# schemTSC.net
KiCad netlist of a schematic drawn in EAGLE
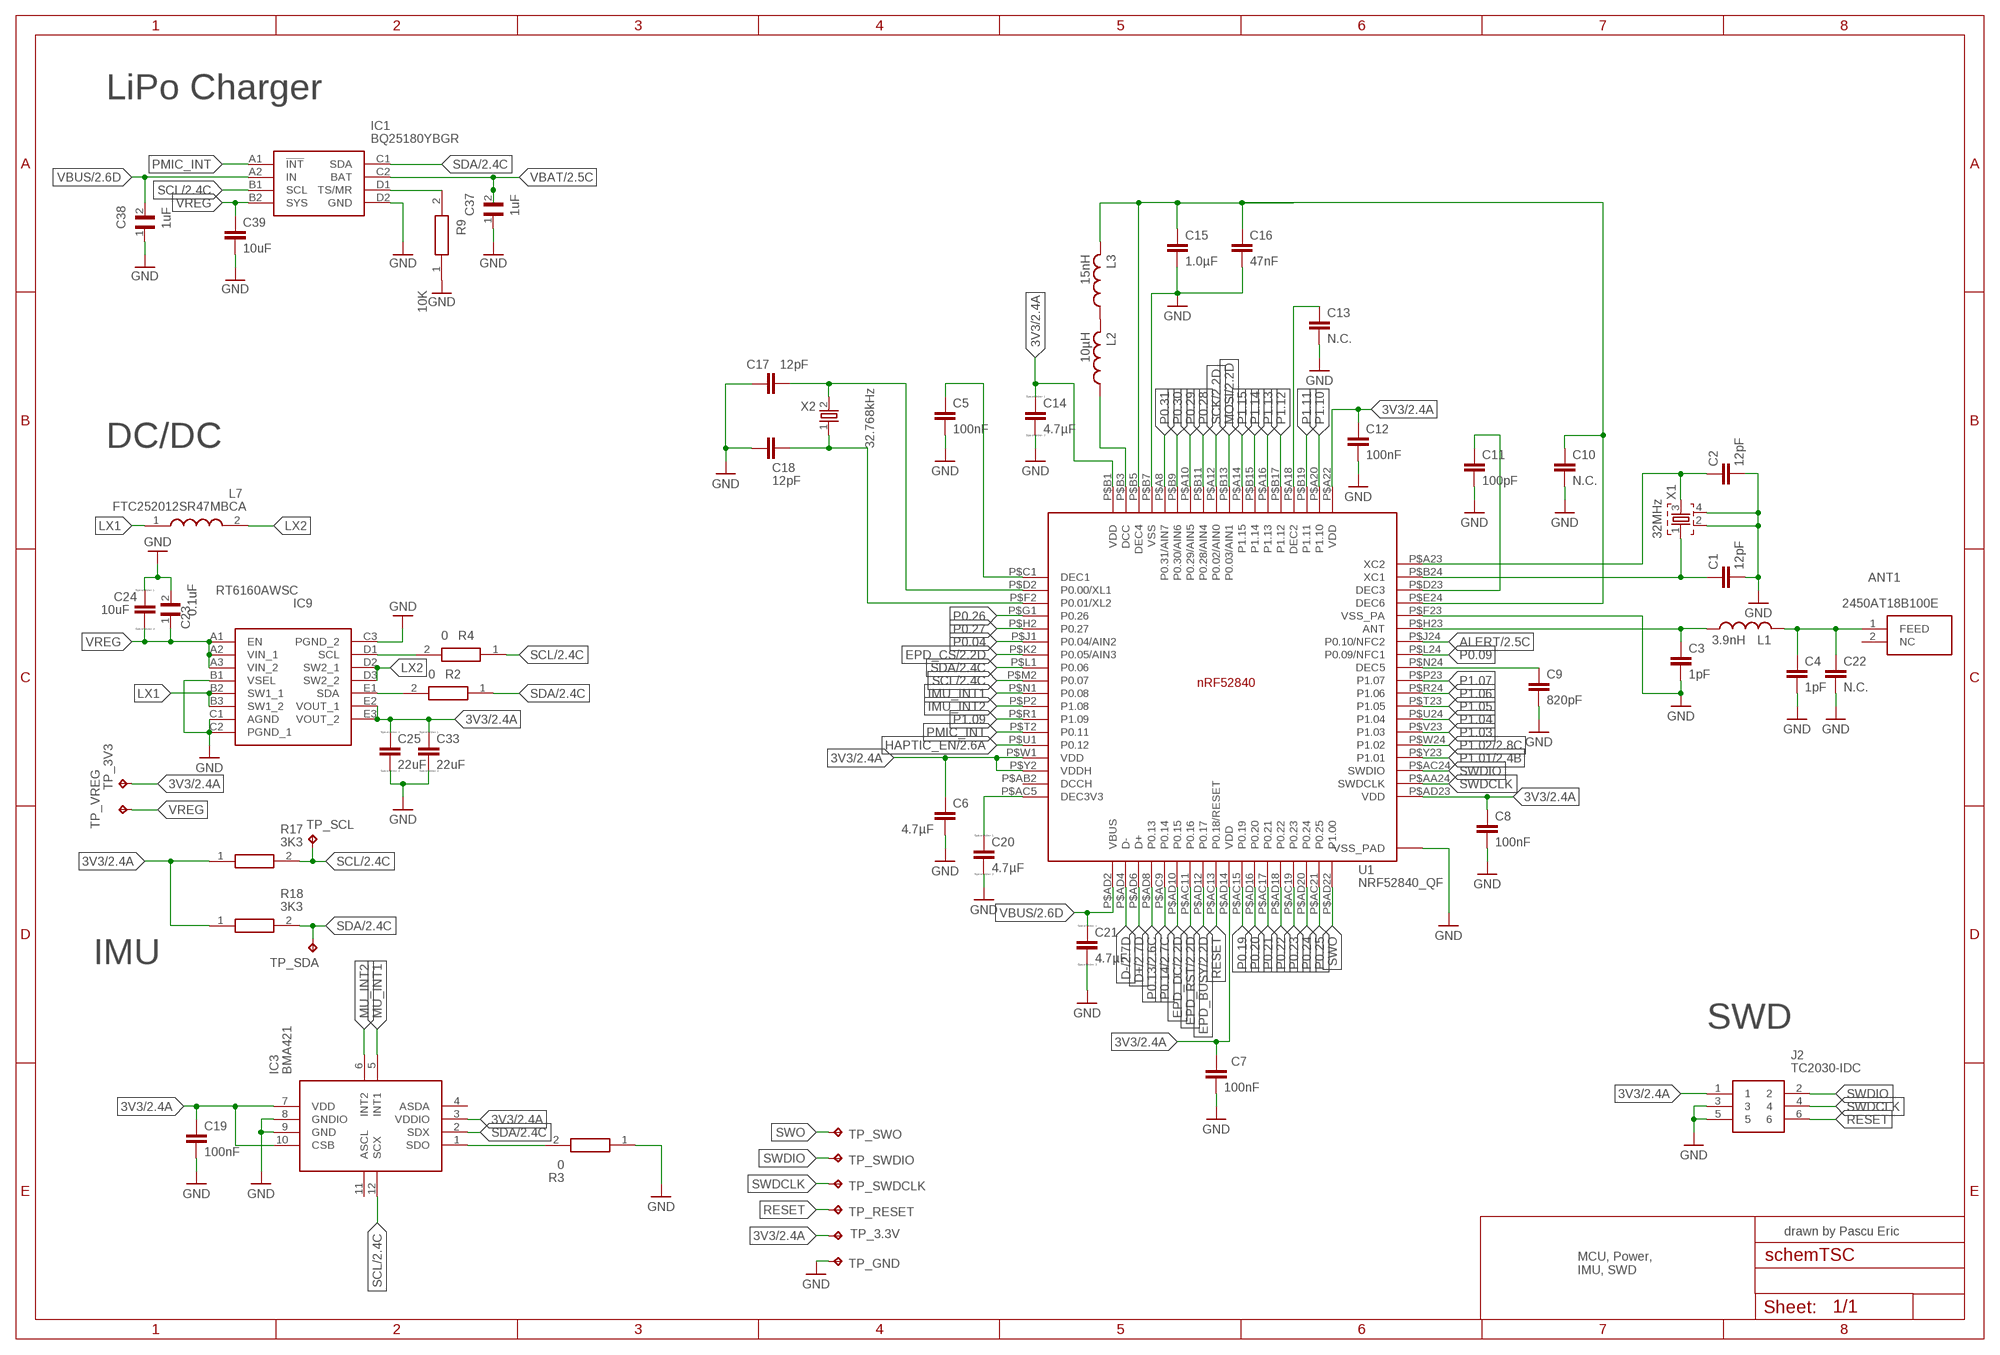
[diagram p0: schematic, sheet 1, part 1 of 2]
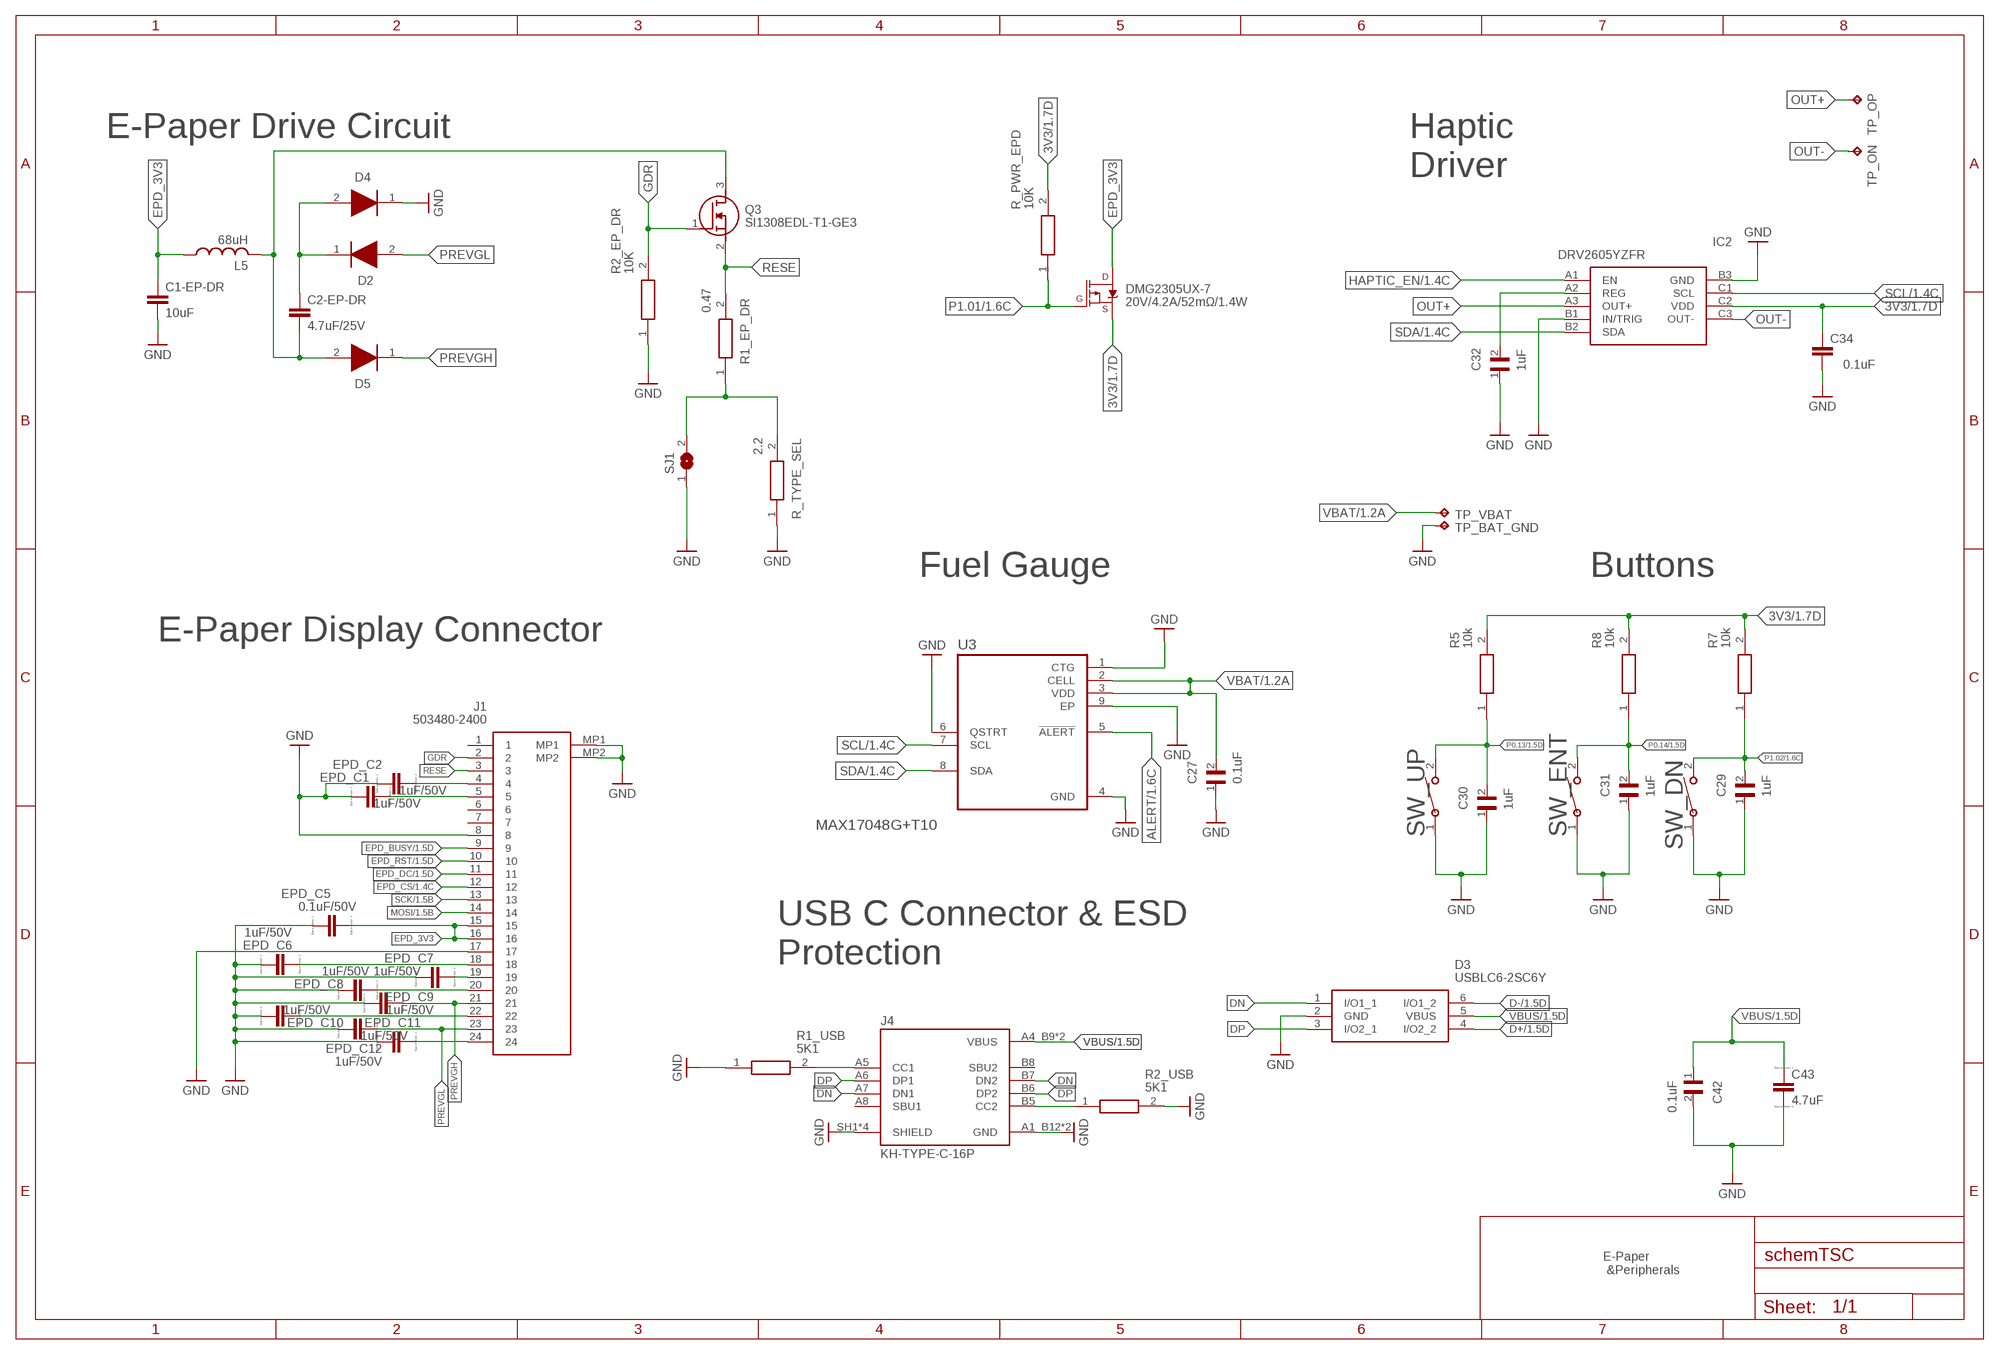
[diagram p1: schematic, sheet 1, part 2 of 2]

(export (version "E")
  (design (tool "Eeschema 10.0.6"))
  (components
    (comp (ref "ANT1")
      (value "2450AT18B100E")
      (footprint "eagle-import:2450AT18B100E_ANTC3216X140N")
      (fields (field (name "MOUSER_PART_NUMBER") "609-2450AT18B100E"))
      (libsource (lib "eagle-import") (part "2450AT18B100E_2450AT18B100E"))
    )
    (comp (ref "C1")
      (value "12pF")
      (footprint "eagle-import:NORDIC_NRF_3_RESC0201_L")
      (libsource (lib "eagle-import") (part "NORDIC_NRF_3_CAPACITOR_0201_L"))
    )
    (comp (ref "C1-EP-DR")
      (value "10uF")
      (footprint "eagle-import:NORDIC_NRF_3_RESC0201_L")
      (libsource (lib "eagle-import") (part "NORDIC_NRF_3_CAPACITOR_0201_L"))
    )
    (comp (ref "C2")
      (value "12pF")
      (footprint "eagle-import:NORDIC_NRF_3_RESC0201_L")
      (libsource (lib "eagle-import") (part "NORDIC_NRF_3_CAPACITOR_0201_L"))
    )
    (comp (ref "C2-EP-DR")
      (value "4.7uF/25V")
      (footprint "eagle-import:NORDIC_NRF_3_RESC0201_L")
      (libsource (lib "eagle-import") (part "NORDIC_NRF_3_CAPACITOR_0201_L"))
    )
    (comp (ref "C3")
      (value "1pF")
      (footprint "eagle-import:NORDIC_NRF_3_RESC0201_L")
      (libsource (lib "eagle-import") (part "NORDIC_NRF_3_CAPACITOR_0201_L"))
    )
    (comp (ref "C4")
      (value "1pF")
      (footprint "eagle-import:NORDIC_NRF_3_RESC0201_L")
      (libsource (lib "eagle-import") (part "NORDIC_NRF_3_CAPACITOR_0201_L"))
    )
    (comp (ref "C5")
      (value "100nF")
      (footprint "eagle-import:NORDIC_NRF_3_RESC0201_L")
      (libsource (lib "eagle-import") (part "NORDIC_NRF_3_CAPACITOR_0201_L"))
    )
    (comp (ref "C6")
      (value "4.7µF")
      (footprint "eagle-import:NORDIC_NRF_3_RESC0201_L")
      (libsource (lib "eagle-import") (part "NORDIC_NRF_3_CAPACITOR_0201_L"))
    )
    (comp (ref "C7")
      (value "100nF")
      (footprint "eagle-import:NORDIC_NRF_3_RESC0201_L")
      (libsource (lib "eagle-import") (part "NORDIC_NRF_3_CAPACITOR_0201_L"))
    )
    (comp (ref "C8")
      (value "100nF")
      (footprint "eagle-import:NORDIC_NRF_3_RESC0201_L")
      (libsource (lib "eagle-import") (part "NORDIC_NRF_3_CAPACITOR_0201_L"))
    )
    (comp (ref "C9")
      (value "820pF")
      (footprint "eagle-import:NORDIC_NRF_3_RESC0201_L")
      (libsource (lib "eagle-import") (part "NORDIC_NRF_3_CAPACITOR_0201_L"))
    )
    (comp (ref "C10")
      (value "N.C.")
      (footprint "eagle-import:NORDIC_NRF_3_RESC0201_L")
      (libsource (lib "eagle-import") (part "NORDIC_NRF_3_CAPACITOR_0201_L"))
    )
    (comp (ref "C11")
      (value "100pF")
      (footprint "eagle-import:NORDIC_NRF_3_RESC0201_L")
      (libsource (lib "eagle-import") (part "NORDIC_NRF_3_CAPACITOR_0201_L"))
    )
    (comp (ref "C12")
      (value "100nF")
      (footprint "eagle-import:NORDIC_NRF_3_RESC0201_L")
      (libsource (lib "eagle-import") (part "NORDIC_NRF_3_CAPACITOR_0201_L"))
    )
    (comp (ref "C13")
      (value "N.C.")
      (footprint "eagle-import:NORDIC_NRF_3_RESC0201_L")
      (libsource (lib "eagle-import") (part "NORDIC_NRF_3_CAPACITOR_0201_L"))
    )
    (comp (ref "C14")
      (value "4.7µF")
      (footprint "eagle-import:ESP32_C6_LIBRARY_1_ESP32_WROVER_EAGLE-LTSPICE_C0402")
      (libsource (lib "eagle-import") (part "ESP32_C6_LIBRARY_1_ESP32_WROVER_EAGLE-LTSPICE_CC0402"))
    )
    (comp (ref "C15")
      (value "1.0µF")
      (footprint "eagle-import:NORDIC_NRF_3_RESC0201_L")
      (libsource (lib "eagle-import") (part "NORDIC_NRF_3_CAPACITOR_0201_L"))
    )
    (comp (ref "C16")
      (value "47nF")
      (footprint "eagle-import:NORDIC_NRF_3_RESC0201_L")
      (libsource (lib "eagle-import") (part "NORDIC_NRF_3_CAPACITOR_0201_L"))
    )
    (comp (ref "C17")
      (value "12pF")
      (footprint "eagle-import:NORDIC_NRF_3_RESC0201_L")
      (libsource (lib "eagle-import") (part "NORDIC_NRF_3_CAPACITOR_0201_L"))
    )
    (comp (ref "C18")
      (value "12pF")
      (footprint "eagle-import:NORDIC_NRF_3_RESC0201_L")
      (libsource (lib "eagle-import") (part "NORDIC_NRF_3_CAPACITOR_0201_L"))
    )
    (comp (ref "C19")
      (value "100nF")
      (footprint "eagle-import:NORDIC_NRF_3_RESC0201_L")
      (libsource (lib "eagle-import") (part "NORDIC_NRF_3_CAPACITOR_0201_L"))
    )
    (comp (ref "C20")
      (value "4.7µF")
      (footprint "eagle-import:ESP32_C6_LIBRARY_1_ESP32_WROVER_EAGLE-LTSPICE_C0402")
      (libsource (lib "eagle-import") (part "ESP32_C6_LIBRARY_1_ESP32_WROVER_EAGLE-LTSPICE_CC0402"))
    )
    (comp (ref "C21")
      (value "4.7µF")
      (footprint "eagle-import:ESP32_C6_LIBRARY_1_ESP32_WROVER_EAGLE-LTSPICE_C0402")
      (libsource (lib "eagle-import") (part "ESP32_C6_LIBRARY_1_ESP32_WROVER_EAGLE-LTSPICE_CC0402"))
    )
    (comp (ref "C22")
      (value "N.C.")
      (footprint "eagle-import:NORDIC_NRF_3_RESC0201_L")
      (libsource (lib "eagle-import") (part "NORDIC_NRF_3_CAPACITOR_0201_L"))
    )
    (comp (ref "C23")
      (value "0.1uF")
      (footprint "eagle-import:GRM011R60J152KE01L_2_CAPC0201X13N")
      (fields (field (name "MF") "Murata") (field (name "MP") "GRM011R60J152KE01L"))
      (libsource (lib "eagle-import") (part "GRM011R60J152KE01L_2_GRM011R60J152KE01L"))
    )
    (comp (ref "C24")
      (value "10uF")
      (footprint "eagle-import:ESP32_C6_LIBRARY_1_ESP32_WROVER_EAGLE-LTSPICE_C0402")
      (libsource (lib "eagle-import") (part "ESP32_C6_LIBRARY_1_ESP32_WROVER_EAGLE-LTSPICE_CC0402"))
    )
    (comp (ref "C25")
      (value "22uF")
      (footprint "eagle-import:ESP32_C6_LIBRARY_1_ESP32_WROVER_EAGLE-LTSPICE_C0402")
      (libsource (lib "eagle-import") (part "ESP32_C6_LIBRARY_1_ESP32_WROVER_EAGLE-LTSPICE_CC0402"))
    )
    (comp (ref "C27")
      (value "0.1uF")
      (footprint "eagle-import:GRM011R60J152KE01L_2_CAPC0201X13N")
      (fields (field (name "MF") "Murata") (field (name "MP") "GRM011R60J152KE01L"))
      (libsource (lib "eagle-import") (part "GRM011R60J152KE01L_2_GRM011R60J152KE01L"))
    )
    (comp (ref "C29")
      (value "1uF")
      (footprint "eagle-import:GRM011R60J152KE01L_2_CAPC0201X13N")
      (fields (field (name "MF") "Murata") (field (name "MP") "GRM011R60J152KE01L"))
      (libsource (lib "eagle-import") (part "GRM011R60J152KE01L_2_GRM011R60J152KE01L"))
    )
    (comp (ref "C30")
      (value "1uF")
      (footprint "eagle-import:GRM011R60J152KE01L_2_CAPC0201X13N")
      (fields (field (name "MF") "Murata") (field (name "MP") "GRM011R60J152KE01L"))
      (libsource (lib "eagle-import") (part "GRM011R60J152KE01L_2_GRM011R60J152KE01L"))
    )
    (comp (ref "C31")
      (value "1uF")
      (footprint "eagle-import:GRM011R60J152KE01L_2_CAPC0201X13N")
      (fields (field (name "MF") "Murata") (field (name "MP") "GRM011R60J152KE01L"))
      (libsource (lib "eagle-import") (part "GRM011R60J152KE01L_2_GRM011R60J152KE01L"))
    )
    (comp (ref "C32")
      (value "1uF")
      (footprint "eagle-import:GRM011R60J152KE01L_2_CAPC0201X13N")
      (fields (field (name "MF") "Murata") (field (name "MP") "GRM011R60J152KE01L"))
      (libsource (lib "eagle-import") (part "GRM011R60J152KE01L_2_GRM011R60J152KE01L"))
    )
    (comp (ref "C33")
      (value "22uF")
      (footprint "eagle-import:ESP32_C6_LIBRARY_1_ESP32_WROVER_EAGLE-LTSPICE_C0402")
      (libsource (lib "eagle-import") (part "ESP32_C6_LIBRARY_1_ESP32_WROVER_EAGLE-LTSPICE_CC0402"))
    )
    (comp (ref "C34")
      (value "0.1uF")
      (footprint "eagle-import:NORDIC_NRF_3_RESC0201_L")
      (libsource (lib "eagle-import") (part "NORDIC_NRF_3_CAPACITOR_0201_L"))
    )
    (comp (ref "C37")
      (value "1uF")
      (footprint "eagle-import:GRM011R60J152KE01L_2_CAPC0201X13N")
      (fields (field (name "MF") "Murata") (field (name "MP") "GRM011R60J152KE01L"))
      (libsource (lib "eagle-import") (part "GRM011R60J152KE01L_2_GRM011R60J152KE01L"))
    )
    (comp (ref "C38")
      (value "1uF")
      (footprint "eagle-import:GRM011R60J152KE01L_2_CAPC0201X13N")
      (fields (field (name "MF") "Murata") (field (name "MP") "GRM011R60J152KE01L"))
      (libsource (lib "eagle-import") (part "GRM011R60J152KE01L_2_GRM011R60J152KE01L"))
    )
    (comp (ref "C39")
      (value "10uF")
      (footprint "eagle-import:NORDIC_NRF_3_RESC0201_L")
      (libsource (lib "eagle-import") (part "NORDIC_NRF_3_CAPACITOR_0201_L"))
    )
    (comp (ref "C42")
      (value "0.1uF")
      (footprint "eagle-import:GRM011R60J152KE01L_2_CAPC0201X13N")
      (fields (field (name "MF") "Murata") (field (name "MP") "GRM011R60J152KE01L"))
      (libsource (lib "eagle-import") (part "GRM011R60J152KE01L_2_GRM011R60J152KE01L"))
    )
    (comp (ref "C43")
      (value "4.7uF")
      (footprint "eagle-import:ESP32_C6_LIBRARY_1_ESP32_WROVER_EAGLE-LTSPICE_C0402")
      (libsource (lib "eagle-import") (part "ESP32_C6_LIBRARY_1_ESP32_WROVER_EAGLE-LTSPICE_CC0402"))
    )
    (comp (ref "D2")
      (value "ESP32_C6_LIBRARY_5_MBR0530")
      (footprint "eagle-import:ESP32_C6_LIBRARY_5_SOD3716X135N")
      (fields (field (name "MF") "ON Semiconductor") (field (name "MP") "MBR0530"))
      (libsource (lib "eagle-import") (part "ESP32_C6_LIBRARY_5_MBR0530"))
    )
    (comp (ref "D3")
      (value "USBLC6-2SC6Y")
      (footprint "eagle-import:ESP32_C6_LIBRARY_3_SOT95P280X145-6N")
      (fields (field (name "MF") "STMicroelectronics"))
      (libsource (lib "eagle-import") (part "ESP32_C6_LIBRARY_3_USBLC6-2SC6Y"))
    )
    (comp (ref "D4")
      (value "ESP32_C6_LIBRARY_5_MBR0530")
      (footprint "eagle-import:ESP32_C6_LIBRARY_5_SOD3716X135N")
      (fields (field (name "MF") "ON Semiconductor") (field (name "MP") "MBR0530"))
      (libsource (lib "eagle-import") (part "ESP32_C6_LIBRARY_5_MBR0530"))
    )
    (comp (ref "D5")
      (value "ESP32_C6_LIBRARY_5_MBR0530")
      (footprint "eagle-import:ESP32_C6_LIBRARY_5_SOD3716X135N")
      (fields (field (name "MF") "ON Semiconductor") (field (name "MP") "MBR0530"))
      (libsource (lib "eagle-import") (part "ESP32_C6_LIBRARY_5_MBR0530"))
    )
    (comp (ref "DMG2305UX-7")
      (value "20V/4.2A/52mΩ/1.4W")
      (footprint "eagle-import:ESP32_C6_LIBRARY_4_ESP32_C6_LIBRARY_4_ESP32_C6_LIBRARY_4_ESP32_C6_LIBRARY_4_ESP32_WROVER_SPARKFUN-DISCRETESEMI_SOT23-3")
      (libsource (lib "eagle-import") (part "ESP32_C6_LIBRARY_4_ESP32_WROVER_SPARKFUN-DISCRETESEMI_MOSFET_PCH-DMG2305UX-7"))
    )
    (comp (ref "EPD_C1")
      (value "1uF/50V")
      (footprint "eagle-import:ESP32_C6_LIBRARY_1_ESP32_WROVER_EAGLE-LTSPICE_C0402")
      (libsource (lib "eagle-import") (part "ESP32_C6_LIBRARY_1_ESP32_WROVER_EAGLE-LTSPICE_CC0402"))
    )
    (comp (ref "EPD_C2")
      (value "1uF/50V")
      (footprint "eagle-import:ESP32_C6_LIBRARY_1_ESP32_WROVER_EAGLE-LTSPICE_C0402")
      (libsource (lib "eagle-import") (part "ESP32_C6_LIBRARY_1_ESP32_WROVER_EAGLE-LTSPICE_CC0402"))
    )
    (comp (ref "EPD_C5")
      (value "0.1uF/50V")
      (footprint "eagle-import:ESP32_C6_LIBRARY_1_ESP32_WROVER_EAGLE-LTSPICE_C0402")
      (libsource (lib "eagle-import") (part "ESP32_C6_LIBRARY_1_ESP32_WROVER_EAGLE-LTSPICE_CC0402"))
    )
    (comp (ref "EPD_C6")
      (value "1uF/50V")
      (footprint "eagle-import:ESP32_C6_LIBRARY_1_ESP32_WROVER_EAGLE-LTSPICE_C0402")
      (libsource (lib "eagle-import") (part "ESP32_C6_LIBRARY_1_ESP32_WROVER_EAGLE-LTSPICE_CC0402"))
    )
    (comp (ref "EPD_C7")
      (value "1uF/50V")
      (footprint "eagle-import:ESP32_C6_LIBRARY_1_ESP32_WROVER_EAGLE-LTSPICE_C0402")
      (libsource (lib "eagle-import") (part "ESP32_C6_LIBRARY_1_ESP32_WROVER_EAGLE-LTSPICE_CC0402"))
    )
    (comp (ref "EPD_C8")
      (value "1uF/50V")
      (footprint "eagle-import:ESP32_C6_LIBRARY_1_ESP32_WROVER_EAGLE-LTSPICE_C0402")
      (libsource (lib "eagle-import") (part "ESP32_C6_LIBRARY_1_ESP32_WROVER_EAGLE-LTSPICE_CC0402"))
    )
    (comp (ref "EPD_C9")
      (value "1uF/50V")
      (footprint "eagle-import:ESP32_C6_LIBRARY_1_ESP32_WROVER_EAGLE-LTSPICE_C0402")
      (libsource (lib "eagle-import") (part "ESP32_C6_LIBRARY_1_ESP32_WROVER_EAGLE-LTSPICE_CC0402"))
    )
    (comp (ref "EPD_C10")
      (value "1uF/50V")
      (footprint "eagle-import:ESP32_C6_LIBRARY_1_ESP32_WROVER_EAGLE-LTSPICE_C0402")
      (libsource (lib "eagle-import") (part "ESP32_C6_LIBRARY_1_ESP32_WROVER_EAGLE-LTSPICE_CC0402"))
    )
    (comp (ref "EPD_C11")
      (value "1uF/50V")
      (footprint "eagle-import:ESP32_C6_LIBRARY_1_ESP32_WROVER_EAGLE-LTSPICE_C0402")
      (libsource (lib "eagle-import") (part "ESP32_C6_LIBRARY_1_ESP32_WROVER_EAGLE-LTSPICE_CC0402"))
    )
    (comp (ref "EPD_C12")
      (value "1uF/50V")
      (footprint "eagle-import:ESP32_C6_LIBRARY_1_ESP32_WROVER_EAGLE-LTSPICE_C0402")
      (libsource (lib "eagle-import") (part "ESP32_C6_LIBRARY_1_ESP32_WROVER_EAGLE-LTSPICE_CC0402"))
    )
    (comp (ref "IC1")
      (value "BQ25180YBGR")
      (footprint "eagle-import:BQ25180YBGR_BGA8C40P2X4_100X155X50")
      (fields (field (name "MOUSER_PART_NUMBER") "595-BQ25180YBGR"))
      (libsource (lib "eagle-import") (part "BQ25180YBGR_BQ25180YBGR"))
    )
    (comp (ref "IC2")
      (value "DRV2605YZFR")
      (footprint "eagle-import:DRV2605YZFR_BGA9C50P3X3_144X144X62")
      (libsource (lib "eagle-import") (part "DRV2605YZFR_DRV2605YZFR"))
    )
    (comp (ref "IC3")
      (value "BMA421")
      (footprint "eagle-import:BMA423_BMA423")
      (fields
        (field (name "MANUFACTURER_PART_NUMBER") "BMA423")
        (field (name "MOUSER_PART_NUMBER") "262-BMA423")
      )
      (libsource (lib "eagle-import") (part "BMA423_BMA423"))
    )
    (comp (ref "IC9")
      (value "RT6160AWSC")
      (footprint "eagle-import:RT6160AWSC_BGA15C40P3X5_140X230X60")
      (fields (field (name "MOUSER_PART_NUMBER") "835-RT6160AWSC"))
      (libsource (lib "eagle-import") (part "RT6160AWSC_RT6160AWSC"))
    )
    (comp (ref "J1")
      (value "503480-2400")
      (footprint "eagle-import:503480-2400_5034802400")
      (fields (field (name "MOUSER_PART_NUMBER") "538-503480-2400"))
      (libsource (lib "eagle-import") (part "503480-2400_503480-2400"))
    )
    (comp (ref "J2")
      (value "TC2030-IDC")
      (footprint "eagle-import:TC2030-IDC_TC2030IDC")
      (libsource (lib "eagle-import") (part "TC2030-IDC_TC2030-IDC"))
    )
    (comp (ref "J4")
      (value "KH-TYPE-C-16P")
      (footprint "eagle-import:KH-TYPE-C-16P_KINGHELM_KH-TYPE-C-16P")
      (fields (field (name "MF") "kinghelm"))
      (libsource (lib "eagle-import") (part "KH-TYPE-C-16P_KH-TYPE-C-16P"))
    )
    (comp (ref "L1")
      (value "3.9nH")
      (footprint "eagle-import:NORDIC_NRF_2_RESC0402_L")
      (libsource (lib "eagle-import") (part "NORDIC_NRF_2_INDUCTOR_0402_L"))
    )
    (comp (ref "L2")
      (value "10µH")
      (footprint "eagle-import:NORDIC_NRF_2_RESC0402_L")
      (libsource (lib "eagle-import") (part "NORDIC_NRF_2_INDUCTOR_0402_L"))
    )
    (comp (ref "L3")
      (value "15nH")
      (footprint "eagle-import:NORDIC_NRF_2_RESC0402_L")
      (libsource (lib "eagle-import") (part "NORDIC_NRF_2_INDUCTOR_0402_L"))
    )
    (comp (ref "L5")
      (value "68uH")
      (footprint "eagle-import:NORDIC_NRF_2_RESC0402_L")
      (libsource (lib "eagle-import") (part "NORDIC_NRF_2_INDUCTOR_0402_L"))
    )
    (comp (ref "L7")
      (value "FTC252012SR47MBCA")
      (footprint "eagle-import:MLP2016SR47MT0S1_INDC2016X100N")
      (libsource (lib "eagle-import") (part "MLP2016SR47MT0S1_FTC252012SR47MBCA"))
    )
    (comp (ref "Q3")
      (value "SI1308EDL-T1-GE3")
      (footprint "eagle-import:ESP32_C6_LIBRARY_6_SOT65P210X110-3N")
      (fields (field (name "MF") "Vishay Siliconix"))
      (libsource (lib "eagle-import") (part "ESP32_C6_LIBRARY_6_SI1308EDL-T1-GE3"))
    )
    (comp (ref "R1_EP_DR")
      (value "0.47")
      (footprint "eagle-import:ERA-1AEB3401C_0201")
      (libsource (lib "eagle-import") (part "ERA-1AEB3401C_CPF0201D7K68C1"))
    )
    (comp (ref "R1_USB")
      (value "5K1")
      (footprint "eagle-import:CPF0201D7K68C1_0201")
      (libsource (lib "eagle-import") (part "CPF0201D7K68C1_CPF0201D7K68C1"))
    )
    (comp (ref "R2")
      (value "0")
      (footprint "eagle-import:CPF0201D7K68C1_0201")
      (libsource (lib "eagle-import") (part "CPF0201D7K68C1_CPF0201D7K68C1"))
    )
    (comp (ref "R2_EP_DR")
      (value "10K")
      (footprint "eagle-import:ERA-1AEB3401C_0201")
      (libsource (lib "eagle-import") (part "ERA-1AEB3401C_CPF0201D7K68C1"))
    )
    (comp (ref "R2_USB")
      (value "5K1")
      (footprint "eagle-import:ERA-1AEB3401C_0201")
      (libsource (lib "eagle-import") (part "ERA-1AEB3401C_CPF0201D7K68C1"))
    )
    (comp (ref "R3")
      (value "0")
      (footprint "eagle-import:ERA-1AEB3401C_0201")
      (libsource (lib "eagle-import") (part "ERA-1AEB3401C_CPF0201D7K68C1"))
    )
    (comp (ref "R4")
      (value "0")
      (footprint "eagle-import:CPF0201D7K68C1_0201")
      (libsource (lib "eagle-import") (part "CPF0201D7K68C1_CPF0201D7K68C1"))
    )
    (comp (ref "R5")
      (value "10k")
      (footprint "eagle-import:CPF0201D7K68C1_0201")
      (libsource (lib "eagle-import") (part "CPF0201D7K68C1_CPF0201D7K68C1"))
    )
    (comp (ref "R7")
      (value "10k")
      (footprint "eagle-import:CPF0201D7K68C1_0201")
      (libsource (lib "eagle-import") (part "CPF0201D7K68C1_CPF0201D7K68C1"))
    )
    (comp (ref "R8")
      (value "10k")
      (footprint "eagle-import:CPF0201D7K68C1_0201")
      (libsource (lib "eagle-import") (part "CPF0201D7K68C1_CPF0201D7K68C1"))
    )
    (comp (ref "R9")
      (value "10K")
      (footprint "eagle-import:ERA-1AEB3401C_0201")
      (libsource (lib "eagle-import") (part "ERA-1AEB3401C_CPF0201D7K68C1"))
    )
    (comp (ref "R17")
      (value "3K3")
      (footprint "eagle-import:CPF0201D7K68C1_0201")
      (libsource (lib "eagle-import") (part "CPF0201D7K68C1_CPF0201D7K68C1"))
    )
    (comp (ref "R18")
      (value "3K3")
      (footprint "eagle-import:CPF0201D7K68C1_0201")
      (libsource (lib "eagle-import") (part "CPF0201D7K68C1_CPF0201D7K68C1"))
    )
    (comp (ref "R_PWR_EPD")
      (value "10K")
      (footprint "eagle-import:CPF0201D7K68C1_0201")
      (libsource (lib "eagle-import") (part "CPF0201D7K68C1_CPF0201D7K68C1"))
    )
    (comp (ref "R_TYPE_SEL")
      (value "2.2")
      (footprint "eagle-import:ERA-1AEB3401C_0201")
      (libsource (lib "eagle-import") (part "ERA-1AEB3401C_CPF0201D7K68C1"))
    )
    (comp (ref "SJ1")
      (value "ESP32_C6_LIBRARY_7_JUMPER_SJ")
      (footprint "eagle-import:ESP32_C6_LIBRARY_7_JUMPER_SJ")
      (libsource (lib "eagle-import") (part "ESP32_C6_LIBRARY_7_JUMPER_SJ"))
    )
    (comp (ref "SW_DN")
      (value "2025-10-22_07-23-44_LIBRARY_EVP-AKE31ASW_EVP-AKE31A_PAN")
      (footprint "eagle-import:2025-10-22_07-23-44_LIBRARY_SW_EVP-AKE31A_PAN")
      (fields
        (field (name "MANUFACTURER_PART_NUMBER") "EVP-AKE31A")
        (field (name "COPYRIGHT") "Copyright (C) 2025 Ultra Librarian. All rights reserved.")
      )
      (libsource (lib "eagle-import") (part "2025-10-22_07-23-44_LIBRARY_EVP-AKE31ASW_EVP-AKE31A_PAN"))
    )
    (comp (ref "SW_ENT")
      (value "2025-10-22_07-23-44_LIBRARY_EVP-AKE31ASW_EVP-AKE31A_PAN")
      (footprint "eagle-import:2025-10-22_07-23-44_LIBRARY_SW_EVP-AKE31A_PAN")
      (fields
        (field (name "MANUFACTURER_PART_NUMBER") "EVP-AKE31A")
        (field (name "COPYRIGHT") "Copyright (C) 2025 Ultra Librarian. All rights reserved.")
      )
      (libsource (lib "eagle-import") (part "2025-10-22_07-23-44_LIBRARY_EVP-AKE31ASW_EVP-AKE31A_PAN"))
    )
    (comp (ref "SW_UP")
      (value "2025-10-22_07-23-44_LIBRARY_EVP-AKE31ASW_EVP-AKE31A_PAN")
      (footprint "eagle-import:2025-10-22_07-23-44_LIBRARY_SW_EVP-AKE31A_PAN")
      (fields
        (field (name "MANUFACTURER_PART_NUMBER") "EVP-AKE31A")
        (field (name "COPYRIGHT") "Copyright (C) 2025 Ultra Librarian. All rights reserved.")
      )
      (libsource (lib "eagle-import") (part "2025-10-22_07-23-44_LIBRARY_EVP-AKE31ASW_EVP-AKE31A_PAN"))
    )
    (comp (ref "TP_3.3V")
      (value "HECTOR_WATCH_1_TPTP20R")
      (footprint "eagle-import:HECTOR_WATCH_1_TP20R")
      (libsource (lib "eagle-import") (part "HECTOR_WATCH_1_TPTP20R"))
    )
    (comp (ref "TP_3V3")
      (value "HECTOR_WATCH_1_TPTP20R")
      (footprint "eagle-import:HECTOR_WATCH_1_TP20R")
      (libsource (lib "eagle-import") (part "HECTOR_WATCH_1_TPTP20R"))
    )
    (comp (ref "TP_BAT_GND")
      (value "HECTOR_WATCH_1_TPTP20R")
      (footprint "eagle-import:HECTOR_WATCH_1_TP20R")
      (libsource (lib "eagle-import") (part "HECTOR_WATCH_1_TPTP20R"))
    )
    (comp (ref "TP_GND")
      (value "HECTOR_WATCH_1_TPTP20R")
      (footprint "eagle-import:HECTOR_WATCH_1_TP20R")
      (libsource (lib "eagle-import") (part "HECTOR_WATCH_1_TPTP20R"))
    )
    (comp (ref "TP_ON")
      (value "HECTOR_WATCH_1_TPTP20R")
      (footprint "eagle-import:HECTOR_WATCH_1_TP20R")
      (libsource (lib "eagle-import") (part "HECTOR_WATCH_1_TPTP20R"))
    )
    (comp (ref "TP_OP")
      (value "HECTOR_WATCH_1_TPTP20R")
      (footprint "eagle-import:HECTOR_WATCH_1_TP20R")
      (libsource (lib "eagle-import") (part "HECTOR_WATCH_1_TPTP20R"))
    )
    (comp (ref "TP_RESET")
      (value "HECTOR_WATCH_1_TPTP20R")
      (footprint "eagle-import:HECTOR_WATCH_1_TP20R")
      (libsource (lib "eagle-import") (part "HECTOR_WATCH_1_TPTP20R"))
    )
    (comp (ref "TP_SCL")
      (value "HECTOR_WATCH_1_TPTP20R")
      (footprint "eagle-import:HECTOR_WATCH_1_TP20R")
      (libsource (lib "eagle-import") (part "HECTOR_WATCH_1_TPTP20R"))
    )
    (comp (ref "TP_SDA")
      (value "HECTOR_WATCH_1_TPTP20R")
      (footprint "eagle-import:HECTOR_WATCH_1_TP20R")
      (libsource (lib "eagle-import") (part "HECTOR_WATCH_1_TPTP20R"))
    )
    (comp (ref "TP_SWDCLK")
      (value "HECTOR_WATCH_1_TPTP20R")
      (footprint "eagle-import:HECTOR_WATCH_1_TP20R")
      (libsource (lib "eagle-import") (part "HECTOR_WATCH_1_TPTP20R"))
    )
    (comp (ref "TP_SWDIO")
      (value "HECTOR_WATCH_1_TPTP20R")
      (footprint "eagle-import:HECTOR_WATCH_1_TP20R")
      (libsource (lib "eagle-import") (part "HECTOR_WATCH_1_TPTP20R"))
    )
    (comp (ref "TP_SWO")
      (value "HECTOR_WATCH_1_TPTP20R")
      (footprint "eagle-import:HECTOR_WATCH_1_TP20R")
      (libsource (lib "eagle-import") (part "HECTOR_WATCH_1_TPTP20R"))
    )
    (comp (ref "TP_VBAT")
      (value "HECTOR_WATCH_1_TPTP20R")
      (footprint "eagle-import:HECTOR_WATCH_1_TP20R")
      (libsource (lib "eagle-import") (part "HECTOR_WATCH_1_TPTP20R"))
    )
    (comp (ref "TP_VREG")
      (value "HECTOR_WATCH_1_TPTP20R")
      (footprint "eagle-import:HECTOR_WATCH_1_TP20R")
      (libsource (lib "eagle-import") (part "HECTOR_WATCH_1_TPTP20R"))
    )
    (comp (ref "U1")
      (value "NRF52840_QF")
      (footprint "eagle-import:NORDIC_NRF_4_AQFN50P700X700X85_HS-74N")
      (libsource (lib "eagle-import") (part "NORDIC_NRF_4_NRF52840_QF"))
    )
    (comp (ref "U3")
      (value "MAX17048G+T10")
      (footprint "eagle-import:ESP32_C6_LIBRARY_SON50P200X200X80-9N")
      (fields (field (name "MF") "Analog Devices"))
      (libsource (lib "eagle-import") (part "ESP32_C6_LIBRARY_MAX17048G+T10"))
    )
    (comp (ref "X1")
      (value "32MHz")
      (footprint "eagle-import:NORDIC_NRF_BT-XTAL_2016_N")
      (libsource (lib "eagle-import") (part "NORDIC_NRF_XTAL_32MHZ"))
    )
    (comp (ref "X2")
      (value "32.768kHz")
      (footprint "eagle-import:NORDIC_NRF_1_XTAL_3215_N")
      (libsource (lib "eagle-import") (part "NORDIC_NRF_1_XTAL_32KHZ"))
    )
  )
  (nets
    (net (code "1") (name "3V3{slash}1.7D") (class "Default")
      (node (ref "C34") (pin "1") (pinfunction "1_1") (pintype "passive"))
      (node (ref "DMG2305UX-7") (pin "2") (pinfunction "S_2") (pintype "bidirectional"))
      (node (ref "IC2") (pin "C2") (pinfunction "VDD_C2") (pintype "bidirectional"))
      (node (ref "R5") (pin "2") (pinfunction "2_2") (pintype "bidirectional"))
      (node (ref "R7") (pin "2") (pinfunction "2_2") (pintype "bidirectional"))
      (node (ref "R8") (pin "2") (pinfunction "2_2") (pintype "bidirectional"))
      (node (ref "R_PWR_EPD") (pin "2") (pinfunction "2_2") (pintype "bidirectional"))
    )
    (net (code "2") (name "3V3{slash}2.4A") (class "Default")
      (node (ref "C12") (pin "1") (pinfunction "1_1") (pintype "passive"))
      (node (ref "C14") (pin "1") (pinfunction "1_1") (pintype "passive"))
      (node (ref "C19") (pin "1") (pinfunction "1_1") (pintype "passive"))
      (node (ref "C25") (pin "1") (pinfunction "1_1") (pintype "passive"))
      (node (ref "C33") (pin "1") (pinfunction "1_1") (pintype "passive"))
      (node (ref "C6") (pin "1") (pinfunction "1_1") (pintype "passive"))
      (node (ref "C7") (pin "1") (pinfunction "1_1") (pintype "passive"))
      (node (ref "C8") (pin "1") (pinfunction "1_1") (pintype "passive"))
      (node (ref "IC3") (pin "10") (pinfunction "CSB_10") (pintype "bidirectional"))
      (node (ref "IC3") (pin "3") (pinfunction "VDDIO_3") (pintype "bidirectional"))
      (node (ref "IC3") (pin "7") (pinfunction "VDD_7") (pintype "bidirectional"))
      (node (ref "IC9") (pin "E2") (pinfunction "VOUT_1_E2") (pintype "bidirectional"))
      (node (ref "IC9") (pin "E3") (pinfunction "VOUT_2_E3") (pintype "bidirectional"))
      (node (ref "J2") (pin "1") (pinfunction "1_1") (pintype "bidirectional"))
      (node (ref "R17") (pin "1") (pinfunction "1_1") (pintype "bidirectional"))
      (node (ref "R18") (pin "1") (pinfunction "1_1") (pintype "bidirectional"))
      (node (ref "TP_3.3V") (pin "TP") (pinfunction "TP_TP") (pintype "input"))
      (node (ref "TP_3V3") (pin "TP") (pinfunction "TP_TP") (pintype "input"))
      (node (ref "U1") (pin "P$A22") (pinfunction "VDD_P$A22") (pintype "power_in"))
      (node (ref "U1") (pin "P$AD14") (pinfunction "VDD_P$AD14") (pintype "power_in"))
      (node (ref "U1") (pin "P$AD23") (pinfunction "VDD_P$AD23") (pintype "power_in"))
      (node (ref "U1") (pin "P$B1") (pinfunction "VDD_P$B1") (pintype "power_in"))
      (node (ref "U1") (pin "P$W1") (pinfunction "VDD_P$W1") (pintype "power_in"))
      (node (ref "U1") (pin "P$Y2") (pinfunction "VDDH_P$Y2") (pintype "power_in"))
    )
    (net (code "3") (name "ALERT{slash}1.6C") (class "Default")
      (node (ref "U3") (pin "5") (pinfunction "~{ALERT}_5") (pintype "output"))
    )
    (net (code "4") (name "ALERT{slash}2.5C") (class "Default")
      (node (ref "U1") (pin "P$J24") (pinfunction "P0.10/NFC2_P$J24") (pintype "bidirectional"))
    )
    (net (code "5") (name "D+{slash}1.5D") (class "Default")
      (node (ref "D3") (pin "4") (pinfunction "I/O2_2_4") (pintype "bidirectional"))
    )
    (net (code "6") (name "D+{slash}2.7D") (class "Default")
      (node (ref "U1") (pin "P$AD6") (pinfunction "D+_P$AD6") (pintype "bidirectional"))
    )
    (net (code "7") (name "D-{slash}1.5D") (class "Default")
      (node (ref "D3") (pin "6") (pinfunction "I/O1_2_6") (pintype "bidirectional"))
    )
    (net (code "8") (name "D-{slash}2.7D") (class "Default")
      (node (ref "U1") (pin "P$AD4") (pinfunction "D-_P$AD4") (pintype "bidirectional"))
    )
    (net (code "9") (name "DN") (class "Default")
      (node (ref "D3") (pin "1") (pinfunction "I/O1_1_1") (pintype "bidirectional"))
      (node (ref "J4") (pin "A7") (pinfunction "DN1_A7") (pintype "bidirectional"))
      (node (ref "J4") (pin "B7") (pinfunction "DN2_B7") (pintype "bidirectional"))
    )
    (net (code "10") (name "DP") (class "Default")
      (node (ref "D3") (pin "3") (pinfunction "I/O2_1_3") (pintype "bidirectional"))
      (node (ref "J4") (pin "A6") (pinfunction "DP1_A6") (pintype "bidirectional"))
      (node (ref "J4") (pin "B6") (pinfunction "DP2_B6") (pintype "bidirectional"))
    )
    (net (code "11") (name "EPD_3V3") (class "Default")
      (node (ref "C1-EP-DR") (pin "1") (pinfunction "1_1") (pintype "passive"))
      (node (ref "DMG2305UX-7") (pin "3") (pinfunction "D_3") (pintype "bidirectional"))
      (node (ref "EPD_C5") (pin "2") (pinfunction "2_2") (pintype "passive"))
      (node (ref "J1") (pin "15") (pinfunction "15_15") (pintype "bidirectional"))
      (node (ref "J1") (pin "16") (pinfunction "16_16") (pintype "bidirectional"))
      (node (ref "L5") (pin "1") (pinfunction "1_1") (pintype "passive"))
    )
    (net (code "12") (name "EPD_BUSY{slash}1.5D") (class "Default")
      (node (ref "J1") (pin "9") (pinfunction "9_9") (pintype "bidirectional"))
    )
    (net (code "13") (name "EPD_BUSY{slash}2.2D") (class "Default")
      (node (ref "U1") (pin "P$AD12") (pinfunction "P0.17_P$AD12") (pintype "bidirectional"))
    )
    (net (code "14") (name "EPD_CS{slash}1.4C") (class "Default")
      (node (ref "J1") (pin "12") (pinfunction "12_12") (pintype "bidirectional"))
    )
    (net (code "15") (name "EPD_CS{slash}2.2D") (class "Default")
      (node (ref "U1") (pin "P$K2") (pinfunction "P0.05/AIN3_P$K2") (pintype "bidirectional"))
    )
    (net (code "16") (name "EPD_DC{slash}1.5D") (class "Default")
      (node (ref "J1") (pin "11") (pinfunction "11_11") (pintype "bidirectional"))
    )
    (net (code "17") (name "EPD_DC{slash}2.2D") (class "Default")
      (node (ref "U1") (pin "P$AD10") (pinfunction "P0.15_P$AD10") (pintype "bidirectional"))
    )
    (net (code "18") (name "EPD_RST{slash}1.5D") (class "Default")
      (node (ref "J1") (pin "10") (pinfunction "10_10") (pintype "bidirectional"))
    )
    (net (code "19") (name "EPD_RST{slash}2.2D") (class "Default")
      (node (ref "U1") (pin "P$AC11") (pinfunction "P0.16_P$AC11") (pintype "bidirectional"))
    )
    (net (code "20") (name "GDR") (class "Default")
      (node (ref "J1") (pin "2") (pinfunction "2_2") (pintype "bidirectional"))
      (node (ref "Q3") (pin "1") (pinfunction "G_1") (pintype "bidirectional"))
      (node (ref "R2_EP_DR") (pin "2") (pinfunction "2_2") (pintype "bidirectional"))
    )
    (net (code "21") (name "GND") (class "Default")
      (node (ref "C1") (pin "2") (pinfunction "2_2") (pintype "passive"))
      (node (ref "C1-EP-DR") (pin "2") (pinfunction "2_2") (pintype "passive"))
      (node (ref "C10") (pin "2") (pinfunction "2_2") (pintype "passive"))
      (node (ref "C11") (pin "2") (pinfunction "2_2") (pintype "passive"))
      (node (ref "C12") (pin "2") (pinfunction "2_2") (pintype "passive"))
      (node (ref "C13") (pin "2") (pinfunction "2_2") (pintype "passive"))
      (node (ref "C14") (pin "2") (pinfunction "2_2") (pintype "passive"))
      (node (ref "C15") (pin "2") (pinfunction "2_2") (pintype "passive"))
      (node (ref "C16") (pin "2") (pinfunction "2_2") (pintype "passive"))
      (node (ref "C17") (pin "1") (pinfunction "1_1") (pintype "passive"))
      (node (ref "C18") (pin "2") (pinfunction "2_2") (pintype "passive"))
      (node (ref "C19") (pin "2") (pinfunction "2_2") (pintype "passive"))
      (node (ref "C2") (pin "2") (pinfunction "2_2") (pintype "passive"))
      (node (ref "C20") (pin "2") (pinfunction "2_2") (pintype "passive"))
      (node (ref "C21") (pin "2") (pinfunction "2_2") (pintype "passive"))
      (node (ref "C22") (pin "2") (pinfunction "2_2") (pintype "passive"))
      (node (ref "C23") (pin "2") (pinfunction "2_2") (pintype "passive"))
      (node (ref "C24") (pin "1") (pinfunction "1_1") (pintype "passive"))
      (node (ref "C25") (pin "2") (pinfunction "2_2") (pintype "passive"))
      (node (ref "C27") (pin "1") (pinfunction "1_1") (pintype "passive"))
      (node (ref "C29") (pin "1") (pinfunction "1_1") (pintype "passive"))
      (node (ref "C3") (pin "2") (pinfunction "2_2") (pintype "passive"))
      (node (ref "C30") (pin "1") (pinfunction "1_1") (pintype "passive"))
      (node (ref "C31") (pin "1") (pinfunction "1_1") (pintype "passive"))
      (node (ref "C32") (pin "1") (pinfunction "1_1") (pintype "passive"))
      (node (ref "C33") (pin "2") (pinfunction "2_2") (pintype "passive"))
      (node (ref "C34") (pin "2") (pinfunction "2_2") (pintype "passive"))
      (node (ref "C37") (pin "1") (pinfunction "1_1") (pintype "passive"))
      (node (ref "C38") (pin "1") (pinfunction "1_1") (pintype "passive"))
      (node (ref "C39") (pin "2") (pinfunction "2_2") (pintype "passive"))
      (node (ref "C4") (pin "2") (pinfunction "2_2") (pintype "passive"))
      (node (ref "C42") (pin "2") (pinfunction "2_2") (pintype "passive"))
      (node (ref "C43") (pin "2") (pinfunction "2_2") (pintype "passive"))
      (node (ref "C5") (pin "2") (pinfunction "2_2") (pintype "passive"))
      (node (ref "C6") (pin "2") (pinfunction "2_2") (pintype "passive"))
      (node (ref "C7") (pin "2") (pinfunction "2_2") (pintype "passive"))
      (node (ref "C8") (pin "2") (pinfunction "2_2") (pintype "passive"))
      (node (ref "C9") (pin "2") (pinfunction "2_2") (pintype "passive"))
      (node (ref "D3") (pin "2") (pinfunction "GND_2") (pintype "bidirectional"))
      (node (ref "D4") (pin "1") (pinfunction "K_1") (pintype "bidirectional"))
      (node (ref "EPD_C1") (pin "1") (pinfunction "1_1") (pintype "passive"))
      (node (ref "EPD_C10") (pin "1") (pinfunction "1_1") (pintype "passive"))
      (node (ref "EPD_C11") (pin "1") (pinfunction "1_1") (pintype "passive"))
      (node (ref "EPD_C12") (pin "1") (pinfunction "1_1") (pintype "passive"))
      (node (ref "EPD_C2") (pin "1") (pinfunction "1_1") (pintype "passive"))
      (node (ref "EPD_C5") (pin "1") (pinfunction "1_1") (pintype "passive"))
      (node (ref "EPD_C6") (pin "1") (pinfunction "1_1") (pintype "passive"))
      (node (ref "EPD_C7") (pin "1") (pinfunction "1_1") (pintype "passive"))
      (node (ref "EPD_C8") (pin "1") (pinfunction "1_1") (pintype "passive"))
      (node (ref "EPD_C9") (pin "1") (pinfunction "1_1") (pintype "passive"))
      (node (ref "IC1") (pin "D2") (pinfunction "GND_D2") (pintype "bidirectional"))
      (node (ref "IC2") (pin "B1") (pinfunction "IN/TRIG_B1") (pintype "bidirectional"))
      (node (ref "IC2") (pin "B3") (pinfunction "GND_B3") (pintype "bidirectional"))
      (node (ref "IC3") (pin "8") (pinfunction "GNDIO_8") (pintype "bidirectional"))
      (node (ref "IC3") (pin "9") (pinfunction "GND_9") (pintype "bidirectional"))
      (node (ref "IC9") (pin "B1") (pinfunction "VSEL_B1") (pintype "bidirectional"))
      (node (ref "IC9") (pin "C1") (pinfunction "AGND_C1") (pintype "bidirectional"))
      (node (ref "IC9") (pin "C2") (pinfunction "PGND_1_C2") (pintype "bidirectional"))
      (node (ref "IC9") (pin "C3") (pinfunction "PGND_2_C3") (pintype "bidirectional"))
      (node (ref "J1") (pin "17") (pinfunction "17_17") (pintype "bidirectional"))
      (node (ref "J1") (pin "8") (pinfunction "8_8") (pintype "bidirectional"))
      (node (ref "J1") (pin "MP1") (pinfunction "MP1_MP1") (pintype "bidirectional"))
      (node (ref "J1") (pin "MP2") (pinfunction "MP2_MP2") (pintype "bidirectional"))
      (node (ref "J2") (pin "3") (pinfunction "3_3") (pintype "bidirectional"))
      (node (ref "J2") (pin "5") (pinfunction "5_5") (pintype "bidirectional"))
      (node (ref "J4") (pin "A12_B1") (pinfunction "GND_A12_B1") (pintype "power_in"))
      (node (ref "J4") (pin "A1_B12") (pinfunction "GND_A1_B12") (pintype "power_in"))
      (node (ref "J4") (pin "SH1") (pinfunction "SHIELD_SH1") (pintype "passive"))
      (node (ref "J4") (pin "SH2") (pinfunction "SHIELD_SH2") (pintype "passive"))
      (node (ref "J4") (pin "SH3") (pinfunction "SHIELD_SH3") (pintype "passive"))
      (node (ref "J4") (pin "SH4") (pinfunction "SHIELD_SH4") (pintype "passive"))
      (node (ref "R1_USB") (pin "1") (pinfunction "1_1") (pintype "bidirectional"))
      (node (ref "R2_EP_DR") (pin "1") (pinfunction "1_1") (pintype "bidirectional"))
      (node (ref "R2_USB") (pin "2") (pinfunction "2_2") (pintype "bidirectional"))
      (node (ref "R3") (pin "1") (pinfunction "1_1") (pintype "bidirectional"))
      (node (ref "R9") (pin "1") (pinfunction "1_1") (pintype "bidirectional"))
      (node (ref "R_TYPE_SEL") (pin "1") (pinfunction "1_1") (pintype "bidirectional"))
      (node (ref "SJ1") (pin "1") (pinfunction "1_1") (pintype "passive"))
      (node (ref "SW_DN") (pin "1") (pinfunction "1_1") (pintype "passive"))
      (node (ref "SW_ENT") (pin "1") (pinfunction "1_1") (pintype "passive"))
      (node (ref "SW_UP") (pin "1") (pinfunction "1_1") (pintype "passive"))
      (node (ref "TP_BAT_GND") (pin "TP") (pinfunction "TP_TP") (pintype "input"))
      (node (ref "TP_GND") (pin "TP") (pinfunction "TP_TP") (pintype "input"))
      (node (ref "U1") (pin "P$74") (pinfunction "VSS_PAD_P$74") (pintype "bidirectional"))
      (node (ref "U1") (pin "P$75") (pinfunction "VSS_PAD_P$75") (pintype "bidirectional"))
      (node (ref "U1") (pin "P$76") (pinfunction "VSS_PAD_P$76") (pintype "bidirectional"))
      (node (ref "U1") (pin "P$77") (pinfunction "VSS_PAD_P$77") (pintype "bidirectional"))
      (node (ref "U1") (pin "P$78") (pinfunction "VSS_PAD_P$78") (pintype "bidirectional"))
      (node (ref "U1") (pin "P$79") (pinfunction "VSS_PAD_P$79") (pintype "bidirectional"))
      (node (ref "U1") (pin "P$80") (pinfunction "VSS_PAD_P$80") (pintype "bidirectional"))
      (node (ref "U1") (pin "P$81") (pinfunction "VSS_PAD_P$81") (pintype "bidirectional"))
      (node (ref "U1") (pin "P$82") (pinfunction "VSS_PAD_P$82") (pintype "bidirectional"))
      (node (ref "U1") (pin "P$83") (pinfunction "VSS_PAD_P$83") (pintype "bidirectional"))
      (node (ref "U1") (pin "P$84") (pinfunction "VSS_PAD_P$84") (pintype "bidirectional"))
      (node (ref "U1") (pin "P$85") (pinfunction "VSS_PAD_P$85") (pintype "bidirectional"))
      (node (ref "U1") (pin "P$86") (pinfunction "VSS_PAD_P$86") (pintype "bidirectional"))
      (node (ref "U1") (pin "P$87") (pinfunction "VSS_PAD_P$87") (pintype "bidirectional"))
      (node (ref "U1") (pin "P$88") (pinfunction "VSS_PAD_P$88") (pintype "bidirectional"))
      (node (ref "U1") (pin "P$89") (pinfunction "VSS_PAD_P$89") (pintype "bidirectional"))
      (node (ref "U1") (pin "P$90") (pinfunction "VSS_PAD_P$90") (pintype "bidirectional"))
      (node (ref "U1") (pin "P$B7") (pinfunction "VSS_P$B7") (pintype "power_in"))
      (node (ref "U1") (pin "P$F23") (pinfunction "VSS_PA_P$F23") (pintype "bidirectional"))
      (node (ref "U3") (pin "1") (pinfunction "CTG_1") (pintype "power_in"))
      (node (ref "U3") (pin "4") (pinfunction "GND_4") (pintype "power_in"))
      (node (ref "U3") (pin "6") (pinfunction "QSTRT_6") (pintype "input"))
      (node (ref "U3") (pin "9") (pinfunction "EP_9") (pintype "power_in"))
      (node (ref "X1") (pin "2") (pinfunction "2_2") (pintype "passive"))
      (node (ref "X1") (pin "4") (pinfunction "4_4") (pintype "passive"))
    )
    (net (code "22") (name "HAPTIC_EN{slash}1.4C") (class "Default")
      (node (ref "IC2") (pin "A1") (pinfunction "EN_A1") (pintype "bidirectional"))
    )
    (net (code "23") (name "HAPTIC_EN{slash}2.6A") (class "Default")
      (node (ref "U1") (pin "P$U1") (pinfunction "P0.12_P$U1") (pintype "bidirectional"))
    )
    (net (code "24") (name "IMU_INT1") (class "Default")
      (node (ref "U1") (pin "P$N1") (pinfunction "P0.08_P$N1") (pintype "bidirectional"))
    )
    (net (code "25") (name "IMU_INT2") (class "Default")
      (node (ref "U1") (pin "P$P2") (pinfunction "P1.08_P$P2") (pintype "bidirectional"))
    )
    (net (code "26") (name "LX1") (class "Default")
      (node (ref "IC9") (pin "B2") (pinfunction "SW1_1_B2") (pintype "bidirectional"))
      (node (ref "IC9") (pin "B3") (pinfunction "SW1_2_B3") (pintype "bidirectional"))
      (node (ref "L7") (pin "1") (pinfunction "1_1") (pintype "bidirectional"))
    )
    (net (code "27") (name "LX2") (class "Default")
      (node (ref "IC9") (pin "D2") (pinfunction "SW2_1_D2") (pintype "bidirectional"))
      (node (ref "IC9") (pin "D3") (pinfunction "SW2_2_D3") (pintype "bidirectional"))
      (node (ref "L7") (pin "2") (pinfunction "2_2") (pintype "bidirectional"))
    )
    (net (code "28") (name "MOSI{slash}1.5B") (class "Default")
      (node (ref "J1") (pin "14") (pinfunction "14_14") (pintype "bidirectional"))
    )
    (net (code "29") (name "MOSI{slash}2.2D") (class "Default")
      (node (ref "U1") (pin "P$B13") (pinfunction "P0.03/AIN1_P$B13") (pintype "bidirectional"))
    )
    (net (code "30") (name "MU_INT1") (class "Default")
      (node (ref "IC3") (pin "5") (pinfunction "INT1_5") (pintype "bidirectional"))
    )
    (net (code "31") (name "MU_INT2") (class "Default")
      (node (ref "IC3") (pin "6") (pinfunction "INT2_6") (pintype "bidirectional"))
    )
    (net (code "32") (name "Net-(ANT1-FEED)") (class "Default")
      (node (ref "ANT1") (pin "1") (pinfunction "FEED_1") (pintype "input"))
      (node (ref "C22") (pin "1") (pinfunction "1_1") (pintype "passive"))
      (node (ref "C4") (pin "1") (pinfunction "1_1") (pintype "passive"))
      (node (ref "L1") (pin "2") (pinfunction "2_2") (pintype "passive"))
    )
    (net (code "33") (name "Net-(D2-K)") (class "Default")
      (node (ref "C2-EP-DR") (pin "1") (pinfunction "1_1") (pintype "passive"))
      (node (ref "D2") (pin "1") (pinfunction "K_1") (pintype "bidirectional"))
      (node (ref "D4") (pin "2") (pinfunction "A_2") (pintype "bidirectional"))
    )
    (net (code "34") (name "Net-(D5-A)") (class "Default")
      (node (ref "C2-EP-DR") (pin "2") (pinfunction "2_2") (pintype "passive"))
      (node (ref "D5") (pin "2") (pinfunction "A_2") (pintype "bidirectional"))
      (node (ref "L5") (pin "2") (pinfunction "2_2") (pintype "passive"))
      (node (ref "Q3") (pin "3") (pinfunction "D_3") (pintype "bidirectional"))
    )
    (net (code "35") (name "Net-(EPD_C1-Pad2)") (class "Default")
      (node (ref "EPD_C1") (pin "2") (pinfunction "2_2") (pintype "passive"))
      (node (ref "J1") (pin "5") (pinfunction "5_5") (pintype "bidirectional"))
    )
    (net (code "36") (name "Net-(EPD_C2-Pad2)") (class "Default")
      (node (ref "EPD_C2") (pin "2") (pinfunction "2_2") (pintype "passive"))
      (node (ref "J1") (pin "4") (pinfunction "4_4") (pintype "bidirectional"))
    )
    (net (code "37") (name "Net-(EPD_C6-Pad2)") (class "Default")
      (node (ref "EPD_C6") (pin "2") (pinfunction "2_2") (pintype "passive"))
      (node (ref "J1") (pin "18") (pinfunction "18_18") (pintype "bidirectional"))
    )
    (net (code "38") (name "Net-(EPD_C7-Pad2)") (class "Default")
      (node (ref "EPD_C7") (pin "2") (pinfunction "2_2") (pintype "passive"))
      (node (ref "J1") (pin "19") (pinfunction "19_19") (pintype "bidirectional"))
    )
    (net (code "39") (name "Net-(EPD_C8-Pad2)") (class "Default")
      (node (ref "EPD_C8") (pin "2") (pinfunction "2_2") (pintype "passive"))
      (node (ref "J1") (pin "20") (pinfunction "20_20") (pintype "bidirectional"))
    )
    (net (code "40") (name "Net-(EPD_C10-Pad2)") (class "Default")
      (node (ref "EPD_C10") (pin "2") (pinfunction "2_2") (pintype "passive"))
      (node (ref "J1") (pin "22") (pinfunction "22_22") (pintype "bidirectional"))
    )
    (net (code "41") (name "Net-(EPD_C12-Pad2)") (class "Default")
      (node (ref "EPD_C12") (pin "2") (pinfunction "2_2") (pintype "passive"))
      (node (ref "J1") (pin "24") (pinfunction "24_24") (pintype "bidirectional"))
    )
    (net (code "42") (name "Net-(IC1-TS{slash}MR)") (class "Default")
      (node (ref "IC1") (pin "D1") (pinfunction "TS/MR_D1") (pintype "bidirectional"))
      (node (ref "R9") (pin "2") (pinfunction "2_2") (pintype "bidirectional"))
    )
    (net (code "43") (name "Net-(IC2-REG)") (class "Default")
      (node (ref "C32") (pin "2") (pinfunction "2_2") (pintype "passive"))
      (node (ref "IC2") (pin "A2") (pinfunction "REG_A2") (pintype "bidirectional"))
    )
    (net (code "44") (name "Net-(IC3-SDO)") (class "Default")
      (node (ref "IC3") (pin "1") (pinfunction "SDO_1") (pintype "bidirectional"))
      (node (ref "R3") (pin "2") (pinfunction "2_2") (pintype "bidirectional"))
    )
    (net (code "45") (name "Net-(IC9-SCL)") (class "Default")
      (node (ref "IC9") (pin "D1") (pinfunction "SCL_D1") (pintype "bidirectional"))
      (node (ref "R4") (pin "2") (pinfunction "2_2") (pintype "bidirectional"))
    )
    (net (code "46") (name "Net-(IC9-SDA)") (class "Default")
      (node (ref "IC9") (pin "E1") (pinfunction "SDA_E1") (pintype "bidirectional"))
      (node (ref "R2") (pin "2") (pinfunction "2_2") (pintype "bidirectional"))
    )
    (net (code "47") (name "Net-(J4-CC1)") (class "Default")
      (node (ref "J4") (pin "A5") (pinfunction "CC1_A5") (pintype "bidirectional"))
      (node (ref "R1_USB") (pin "2") (pinfunction "2_2") (pintype "bidirectional"))
    )
    (net (code "48") (name "Net-(J4-CC2)") (class "Default")
      (node (ref "J4") (pin "B5") (pinfunction "CC2_B5") (pintype "bidirectional"))
      (node (ref "R2_USB") (pin "1") (pinfunction "1_1") (pintype "bidirectional"))
    )
    (net (code "49") (name "Net-(L2-Pad2)") (class "Default")
      (node (ref "L2") (pin "2") (pinfunction "2_2") (pintype "passive"))
      (node (ref "L3") (pin "1") (pinfunction "1_1") (pintype "passive"))
    )
    (net (code "50") (name "Net-(R1_EP_DR-Pad1)") (class "Default")
      (node (ref "R1_EP_DR") (pin "1") (pinfunction "1_1") (pintype "bidirectional"))
      (node (ref "R_TYPE_SEL") (pin "2") (pinfunction "2_2") (pintype "bidirectional"))
      (node (ref "SJ1") (pin "2") (pinfunction "2_2") (pintype "passive"))
    )
    (net (code "51") (name "Net-(U1-ANT)") (class "Default")
      (node (ref "C3") (pin "1") (pinfunction "1_1") (pintype "passive"))
      (node (ref "L1") (pin "1") (pinfunction "1_1") (pintype "passive"))
      (node (ref "U1") (pin "P$H23") (pinfunction "ANT_P$H23") (pintype "bidirectional"))
    )
    (net (code "52") (name "Net-(U1-DCC)") (class "Default")
      (node (ref "L2") (pin "1") (pinfunction "1_1") (pintype "passive"))
      (node (ref "U1") (pin "P$B3") (pinfunction "DCC_P$B3") (pintype "output"))
    )
    (net (code "53") (name "Net-(U1-DEC1)") (class "Default")
      (node (ref "C5") (pin "1") (pinfunction "1_1") (pintype "passive"))
      (node (ref "U1") (pin "P$C1") (pinfunction "DEC1_P$C1") (pintype "power_in"))
    )
    (net (code "54") (name "Net-(U1-DEC2)") (class "Default")
      (node (ref "C13") (pin "1") (pinfunction "1_1") (pintype "passive"))
      (node (ref "U1") (pin "P$A18") (pinfunction "DEC2_P$A18") (pintype "bidirectional"))
    )
    (net (code "55") (name "Net-(U1-DEC3)") (class "Default")
      (node (ref "C11") (pin "1") (pinfunction "1_1") (pintype "passive"))
      (node (ref "U1") (pin "P$D23") (pinfunction "DEC3_P$D23") (pintype "bidirectional"))
    )
    (net (code "56") (name "Net-(U1-DEC3V3)") (class "Default")
      (node (ref "C20") (pin "1") (pinfunction "1_1") (pintype "passive"))
      (node (ref "U1") (pin "P$AC5") (pinfunction "DEC3V3_P$AC5") (pintype "bidirectional"))
    )
    (net (code "57") (name "Net-(U1-DEC4)") (class "Default")
      (node (ref "C10") (pin "1") (pinfunction "1_1") (pintype "passive"))
      (node (ref "C15") (pin "1") (pinfunction "1_1") (pintype "passive"))
      (node (ref "C16") (pin "1") (pinfunction "1_1") (pintype "passive"))
      (node (ref "L3") (pin "2") (pinfunction "2_2") (pintype "passive"))
      (node (ref "U1") (pin "P$B5") (pinfunction "DEC4_P$B5") (pintype "power_in"))
      (node (ref "U1") (pin "P$E24") (pinfunction "DEC6_P$E24") (pintype "bidirectional"))
    )
    (net (code "58") (name "Net-(U1-DEC5)") (class "Default")
      (node (ref "C9") (pin "1") (pinfunction "1_1") (pintype "passive"))
      (node (ref "U1") (pin "P$N24") (pinfunction "DEC5_P$N24") (pintype "bidirectional"))
    )
    (net (code "59") (name "Net-(U1-P0.00{slash}XL1)") (class "Default")
      (node (ref "C17") (pin "2") (pinfunction "2_2") (pintype "passive"))
      (node (ref "U1") (pin "P$D2") (pinfunction "P0.00/XL1_P$D2") (pintype "bidirectional"))
      (node (ref "X2") (pin "2") (pinfunction "2_2") (pintype "passive"))
    )
    (net (code "60") (name "Net-(U1-P0.01{slash}XL2)") (class "Default")
      (node (ref "C18") (pin "1") (pinfunction "1_1") (pintype "passive"))
      (node (ref "U1") (pin "P$F2") (pinfunction "P0.01/XL2_P$F2") (pintype "bidirectional"))
      (node (ref "X2") (pin "1") (pinfunction "1_1") (pintype "passive"))
    )
    (net (code "61") (name "Net-(U1-XC1)") (class "Default")
      (node (ref "C1") (pin "1") (pinfunction "1_1") (pintype "passive"))
      (node (ref "U1") (pin "P$B24") (pinfunction "XC1_P$B24") (pintype "input"))
      (node (ref "X1") (pin "1") (pinfunction "1_1") (pintype "passive"))
    )
    (net (code "62") (name "Net-(U1-XC2)") (class "Default")
      (node (ref "C2") (pin "1") (pinfunction "1_1") (pintype "passive"))
      (node (ref "U1") (pin "P$A23") (pinfunction "XC2_P$A23") (pintype "output"))
      (node (ref "X1") (pin "3") (pinfunction "3_3") (pintype "passive"))
    )
    (net (code "63") (name "OUT+") (class "Default")
      (node (ref "IC2") (pin "A3") (pinfunction "OUT+_A3") (pintype "bidirectional"))
      (node (ref "TP_OP") (pin "TP") (pinfunction "TP_TP") (pintype "input"))
    )
    (net (code "64") (name "OUT-") (class "Default")
      (node (ref "IC2") (pin "C3") (pinfunction "OUT-_C3") (pintype "bidirectional"))
      (node (ref "TP_ON") (pin "TP") (pinfunction "TP_TP") (pintype "input"))
    )
    (net (code "65") (name "P0.04") (class "Default")
      (node (ref "U1") (pin "P$J1") (pinfunction "P0.04/AIN2_P$J1") (pintype "bidirectional"))
    )
    (net (code "66") (name "P0.09") (class "Default")
      (node (ref "U1") (pin "P$L24") (pinfunction "P0.09/NFC1_P$L24") (pintype "bidirectional"))
    )
    (net (code "67") (name "P0.13{slash}1.5D") (class "Default")
      (node (ref "C30") (pin "2") (pinfunction "2_2") (pintype "passive"))
      (node (ref "R5") (pin "1") (pinfunction "1_1") (pintype "bidirectional"))
      (node (ref "SW_UP") (pin "2") (pinfunction "2_2") (pintype "passive"))
    )
    (net (code "68") (name "P0.13{slash}2.6C") (class "Default")
      (node (ref "U1") (pin "P$AD8") (pinfunction "P0.13_P$AD8") (pintype "bidirectional"))
    )
    (net (code "69") (name "P0.14{slash}1.5D") (class "Default")
      (node (ref "C31") (pin "2") (pinfunction "2_2") (pintype "passive"))
      (node (ref "R8") (pin "1") (pinfunction "1_1") (pintype "bidirectional"))
      (node (ref "SW_ENT") (pin "2") (pinfunction "2_2") (pintype "passive"))
    )
    (net (code "70") (name "P0.14{slash}2.7C") (class "Default")
      (node (ref "U1") (pin "P$AC9") (pinfunction "P0.14_P$AC9") (pintype "bidirectional"))
    )
    (net (code "71") (name "P0.19") (class "Default")
      (node (ref "U1") (pin "P$AC15") (pinfunction "P0.19_P$AC15") (pintype "bidirectional"))
    )
    (net (code "72") (name "P0.20") (class "Default")
      (node (ref "U1") (pin "P$AD16") (pinfunction "P0.20_P$AD16") (pintype "bidirectional"))
    )
    (net (code "73") (name "P0.21") (class "Default")
      (node (ref "U1") (pin "P$AC17") (pinfunction "P0.21_P$AC17") (pintype "bidirectional"))
    )
    (net (code "74") (name "P0.22") (class "Default")
      (node (ref "U1") (pin "P$AD18") (pinfunction "P0.22_P$AD18") (pintype "bidirectional"))
    )
    (net (code "75") (name "P0.23") (class "Default")
      (node (ref "U1") (pin "P$AC19") (pinfunction "P0.23_P$AC19") (pintype "bidirectional"))
    )
    (net (code "76") (name "P0.24") (class "Default")
      (node (ref "U1") (pin "P$AD20") (pinfunction "P0.24_P$AD20") (pintype "bidirectional"))
    )
    (net (code "77") (name "P0.25") (class "Default")
      (node (ref "U1") (pin "P$AC21") (pinfunction "P0.25_P$AC21") (pintype "bidirectional"))
    )
    (net (code "78") (name "P0.26") (class "Default")
      (node (ref "U1") (pin "P$G1") (pinfunction "P0.26_P$G1") (pintype "bidirectional"))
    )
    (net (code "79") (name "P0.27") (class "Default")
      (node (ref "U1") (pin "P$H2") (pinfunction "P0.27_P$H2") (pintype "bidirectional"))
    )
    (net (code "80") (name "P0.28") (class "Default")
      (node (ref "U1") (pin "P$B11") (pinfunction "P0.28/AIN4_P$B11") (pintype "bidirectional"))
    )
    (net (code "81") (name "P0.29") (class "Default")
      (node (ref "U1") (pin "P$A10") (pinfunction "P0.29/AIN5_P$A10") (pintype "bidirectional"))
    )
    (net (code "82") (name "P0.30") (class "Default")
      (node (ref "U1") (pin "P$B9") (pinfunction "P0.30/AIN6_P$B9") (pintype "bidirectional"))
    )
    (net (code "83") (name "P0.31") (class "Default")
      (node (ref "U1") (pin "P$A8") (pinfunction "P0.31/AIN7_P$A8") (pintype "bidirectional"))
    )
    (net (code "84") (name "P1.01{slash}1.6C") (class "Default")
      (node (ref "DMG2305UX-7") (pin "1") (pinfunction "G_1") (pintype "bidirectional"))
      (node (ref "R_PWR_EPD") (pin "1") (pinfunction "1_1") (pintype "bidirectional"))
    )
    (net (code "85") (name "P1.01{slash}2.4B") (class "Default")
      (node (ref "U1") (pin "P$Y23") (pinfunction "P1.01_P$Y23") (pintype "bidirectional"))
    )
    (net (code "86") (name "P1.02{slash}1.6C") (class "Default")
      (node (ref "C29") (pin "2") (pinfunction "2_2") (pintype "passive"))
      (node (ref "R7") (pin "1") (pinfunction "1_1") (pintype "bidirectional"))
      (node (ref "SW_DN") (pin "2") (pinfunction "2_2") (pintype "passive"))
    )
    (net (code "87") (name "P1.02{slash}2.8C") (class "Default")
      (node (ref "U1") (pin "P$W24") (pinfunction "P1.02_P$W24") (pintype "bidirectional"))
    )
    (net (code "88") (name "P1.03") (class "Default")
      (node (ref "U1") (pin "P$V23") (pinfunction "P1.03_P$V23") (pintype "bidirectional"))
    )
    (net (code "89") (name "P1.04") (class "Default")
      (node (ref "U1") (pin "P$U24") (pinfunction "P1.04_P$U24") (pintype "bidirectional"))
    )
    (net (code "90") (name "P1.05") (class "Default")
      (node (ref "U1") (pin "P$T23") (pinfunction "P1.05_P$T23") (pintype "bidirectional"))
    )
    (net (code "91") (name "P1.06") (class "Default")
      (node (ref "U1") (pin "P$R24") (pinfunction "P1.06_P$R24") (pintype "bidirectional"))
    )
    (net (code "92") (name "P1.07") (class "Default")
      (node (ref "U1") (pin "P$P23") (pinfunction "P1.07_P$P23") (pintype "bidirectional"))
    )
    (net (code "93") (name "P1.09") (class "Default")
      (node (ref "U1") (pin "P$R1") (pinfunction "P1.09_P$R1") (pintype "bidirectional"))
    )
    (net (code "94") (name "P1.10") (class "Default")
      (node (ref "U1") (pin "P$A20") (pinfunction "P1.10_P$A20") (pintype "bidirectional"))
    )
    (net (code "95") (name "P1.11") (class "Default")
      (node (ref "U1") (pin "P$B19") (pinfunction "P1.11_P$B19") (pintype "bidirectional"))
    )
    (net (code "96") (name "P1.12") (class "Default")
      (node (ref "U1") (pin "P$B17") (pinfunction "P1.12_P$B17") (pintype "bidirectional"))
    )
    (net (code "97") (name "P1.13") (class "Default")
      (node (ref "U1") (pin "P$A16") (pinfunction "P1.13_P$A16") (pintype "bidirectional"))
    )
    (net (code "98") (name "P1.14") (class "Default")
      (node (ref "U1") (pin "P$B15") (pinfunction "P1.14_P$B15") (pintype "bidirectional"))
    )
    (net (code "99") (name "P1.15") (class "Default")
      (node (ref "U1") (pin "P$A14") (pinfunction "P1.15_P$A14") (pintype "bidirectional"))
    )
    (net (code "100") (name "PMIC_INT") (class "Default")
      (node (ref "IC1") (pin "A1") (pinfunction "~{INT}_A1") (pintype "bidirectional"))
      (node (ref "U1") (pin "P$T2") (pinfunction "P0.11_P$T2") (pintype "bidirectional"))
    )
    (net (code "101") (name "PREVGH") (class "Default")
      (node (ref "D5") (pin "1") (pinfunction "K_1") (pintype "bidirectional"))
      (node (ref "EPD_C9") (pin "2") (pinfunction "2_2") (pintype "passive"))
      (node (ref "J1") (pin "21") (pinfunction "21_21") (pintype "bidirectional"))
    )
    (net (code "102") (name "PREVGL") (class "Default")
      (node (ref "D2") (pin "2") (pinfunction "A_2") (pintype "bidirectional"))
      (node (ref "EPD_C11") (pin "2") (pinfunction "2_2") (pintype "passive"))
      (node (ref "J1") (pin "23") (pinfunction "23_23") (pintype "bidirectional"))
    )
    (net (code "103") (name "RESE") (class "Default")
      (node (ref "J1") (pin "3") (pinfunction "3_3") (pintype "bidirectional"))
      (node (ref "Q3") (pin "2") (pinfunction "S_2") (pintype "bidirectional"))
      (node (ref "R1_EP_DR") (pin "2") (pinfunction "2_2") (pintype "bidirectional"))
    )
    (net (code "104") (name "RESET") (class "Default")
      (node (ref "J2") (pin "6") (pinfunction "6_6") (pintype "bidirectional"))
      (node (ref "TP_RESET") (pin "TP") (pinfunction "TP_TP") (pintype "input"))
      (node (ref "U1") (pin "P$AC13") (pinfunction "P0.18/RESET_P$AC13") (pintype "bidirectional"))
    )
    (net (code "105") (name "SCK{slash}1.5B") (class "Default")
      (node (ref "J1") (pin "13") (pinfunction "13_13") (pintype "bidirectional"))
    )
    (net (code "106") (name "SCK{slash}2.2D") (class "Default")
      (node (ref "U1") (pin "P$A12") (pinfunction "P0.02/AIN0_P$A12") (pintype "bidirectional"))
    )
    (net (code "107") (name "SCL{slash}1.4C") (class "Default")
      (node (ref "IC2") (pin "C1") (pinfunction "SCL_C1") (pintype "bidirectional"))
      (node (ref "U3") (pin "7") (pinfunction "SCL_7") (pintype "input"))
    )
    (net (code "108") (name "SCL{slash}2.4C") (class "Default")
      (node (ref "IC1") (pin "B1") (pinfunction "SCL_B1") (pintype "bidirectional"))
      (node (ref "IC3") (pin "12") (pinfunction "SCX_12") (pintype "bidirectional"))
      (node (ref "R17") (pin "2") (pinfunction "2_2") (pintype "bidirectional"))
      (node (ref "R4") (pin "1") (pinfunction "1_1") (pintype "bidirectional"))
      (node (ref "TP_SCL") (pin "TP") (pinfunction "TP_TP") (pintype "input"))
      (node (ref "U1") (pin "P$M2") (pinfunction "P0.07_P$M2") (pintype "bidirectional"))
    )
    (net (code "109") (name "SDA{slash}1.4C") (class "Default")
      (node (ref "IC2") (pin "B2") (pinfunction "SDA_B2") (pintype "bidirectional"))
      (node (ref "U3") (pin "8") (pinfunction "SDA_8") (pintype "bidirectional"))
    )
    (net (code "110") (name "SDA{slash}2.4C") (class "Default")
      (node (ref "IC1") (pin "C1") (pinfunction "SDA_C1") (pintype "bidirectional"))
      (node (ref "IC3") (pin "2") (pinfunction "SDX_2") (pintype "bidirectional"))
      (node (ref "R18") (pin "2") (pinfunction "2_2") (pintype "bidirectional"))
      (node (ref "R2") (pin "1") (pinfunction "1_1") (pintype "bidirectional"))
      (node (ref "TP_SDA") (pin "TP") (pinfunction "TP_TP") (pintype "input"))
      (node (ref "U1") (pin "P$L1") (pinfunction "P0.06_P$L1") (pintype "bidirectional"))
    )
    (net (code "111") (name "SWDCLK") (class "Default")
      (node (ref "J2") (pin "4") (pinfunction "4_4") (pintype "bidirectional"))
      (node (ref "TP_SWDCLK") (pin "TP") (pinfunction "TP_TP") (pintype "input"))
      (node (ref "U1") (pin "P$AA24") (pinfunction "SWDCLK_P$AA24") (pintype "input"))
    )
    (net (code "112") (name "SWDIO") (class "Default")
      (node (ref "J2") (pin "2") (pinfunction "2_2") (pintype "bidirectional"))
      (node (ref "TP_SWDIO") (pin "TP") (pinfunction "TP_TP") (pintype "input"))
      (node (ref "U1") (pin "P$AC24") (pinfunction "SWDIO_P$AC24") (pintype "bidirectional"))
    )
    (net (code "113") (name "SWO") (class "Default")
      (node (ref "TP_SWO") (pin "TP") (pinfunction "TP_TP") (pintype "input"))
      (node (ref "U1") (pin "P$AD22") (pinfunction "P1.00_P$AD22") (pintype "bidirectional"))
    )
    (net (code "114") (name "VBAT{slash}1.2A") (class "Default")
      (node (ref "C27") (pin "2") (pinfunction "2_2") (pintype "passive"))
      (node (ref "TP_VBAT") (pin "TP") (pinfunction "TP_TP") (pintype "input"))
      (node (ref "U3") (pin "2") (pinfunction "CELL_2") (pintype "power_in"))
      (node (ref "U3") (pin "3") (pinfunction "VDD_3") (pintype "power_in"))
    )
    (net (code "115") (name "VBAT{slash}2.5C") (class "Default")
      (node (ref "C37") (pin "2") (pinfunction "2_2") (pintype "passive"))
      (node (ref "IC1") (pin "C2") (pinfunction "BAT_C2") (pintype "bidirectional"))
    )
    (net (code "116") (name "VBUS{slash}1.5D") (class "Default")
      (node (ref "C42") (pin "1") (pinfunction "1_1") (pintype "passive"))
      (node (ref "C43") (pin "1") (pinfunction "1_1") (pintype "passive"))
      (node (ref "D3") (pin "5") (pinfunction "VBUS_5") (pintype "bidirectional"))
      (node (ref "J4") (pin "A4_B9") (pinfunction "VBUS_A4_B9") (pintype "power_in"))
      (node (ref "J4") (pin "A9_B4") (pinfunction "VBUS_A9_B4") (pintype "power_in"))
    )
    (net (code "117") (name "VBUS{slash}2.6D") (class "Default")
      (node (ref "C21") (pin "1") (pinfunction "1_1") (pintype "passive"))
      (node (ref "C38") (pin "2") (pinfunction "2_2") (pintype "passive"))
      (node (ref "IC1") (pin "A2") (pinfunction "IN_A2") (pintype "bidirectional"))
      (node (ref "U1") (pin "P$AD2") (pinfunction "VBUS_P$AD2") (pintype "power_in"))
    )
    (net (code "118") (name "VREG") (class "Default")
      (node (ref "C23") (pin "1") (pinfunction "1_1") (pintype "passive"))
      (node (ref "C24") (pin "2") (pinfunction "2_2") (pintype "passive"))
      (node (ref "C39") (pin "1") (pinfunction "1_1") (pintype "passive"))
      (node (ref "IC1") (pin "B2") (pinfunction "SYS_B2") (pintype "bidirectional"))
      (node (ref "IC9") (pin "A1") (pinfunction "EN_A1") (pintype "bidirectional"))
      (node (ref "IC9") (pin "A2") (pinfunction "VIN_1_A2") (pintype "bidirectional"))
      (node (ref "IC9") (pin "A3") (pinfunction "VIN_2_A3") (pintype "bidirectional"))
      (node (ref "TP_VREG") (pin "TP") (pinfunction "TP_TP") (pintype "input"))
    )
    (net (code "119") (name "unconnected-(ANT1-NC-Pad2)") (class "Default")
      (node (ref "ANT1") (pin "2") (pinfunction "NC_2") (pintype "no_connect"))
    )
    (net (code "120") (name "unconnected-(IC3-ASCL-Pad11)") (class "Default")
      (node (ref "IC3") (pin "11") (pinfunction "ASCL_11") (pintype "bidirectional"))
    )
    (net (code "121") (name "unconnected-(IC3-ASDA-Pad4)") (class "Default")
      (node (ref "IC3") (pin "4") (pinfunction "ASDA_4") (pintype "bidirectional"))
    )
    (net (code "122") (name "unconnected-(J1-Pad1)") (class "Default")
      (node (ref "J1") (pin "1") (pinfunction "1_1") (pintype "bidirectional"))
    )
    (net (code "123") (name "unconnected-(J1-Pad6)") (class "Default")
      (node (ref "J1") (pin "6") (pinfunction "6_6") (pintype "bidirectional"))
    )
    (net (code "124") (name "unconnected-(J1-Pad7)") (class "Default")
      (node (ref "J1") (pin "7") (pinfunction "7_7") (pintype "bidirectional"))
    )
    (net (code "125") (name "unconnected-(J4-SBU1-PadA8)") (class "Default")
      (node (ref "J4") (pin "A8") (pinfunction "SBU1_A8") (pintype "bidirectional"))
    )
    (net (code "126") (name "unconnected-(J4-SBU2-PadB8)") (class "Default")
      (node (ref "J4") (pin "B8") (pinfunction "SBU2_B8") (pintype "bidirectional"))
    )
    (net (code "127") (name "unconnected-(U1-DCCH-PadP$AB2)") (class "Default")
      (node (ref "U1") (pin "P$AB2") (pinfunction "DCCH_P$AB2") (pintype "bidirectional"))
    )
  )
)
